# MAIN-FAN.net
KiCad netlist of a schematic drawn in Altium Designer
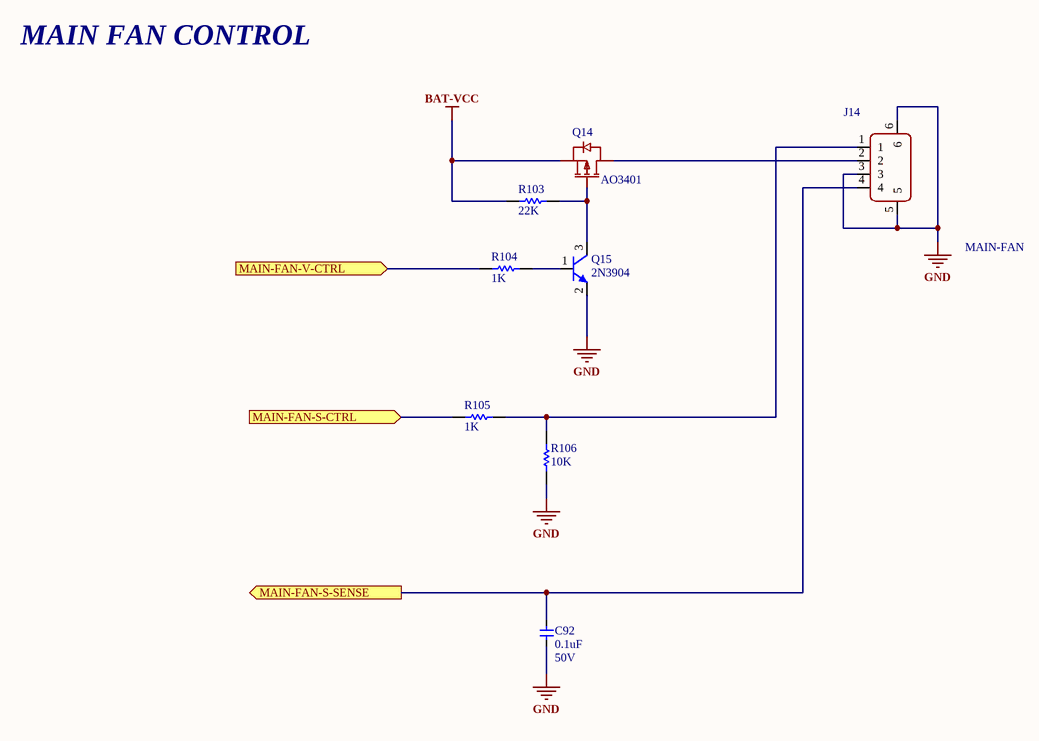
[diagram p0: MAIN-FAN .SchDoc]

(export (version "E")
  (design (tool "Eeschema 10.0.6"))
  (components
    (comp (ref "C92")
      (value "0.1uF")
      (footprint "CAP-0402")
      (fields (field (name "VOLTAGERATE") "50V"))
      (libsource (lib "DesignLibrary") (part "Capacitor-1"))
    )
    (comp (ref "J14")
      (value "MAIN-FAN")
      (footprint "CONN-SMD_4P-P2.00_XUNPU_WAFER-PH2.0-4PWB")
      (libsource (lib "DesignLibrary") (part "HDRx4"))
    )
    (comp (ref "Q14")
      (value "AO3401")
      (footprint "SOT23-3D")
      (libsource (lib "DesignLibrary") (part "P-MOS-SOT23"))
    )
    (comp (ref "Q15")
      (value "2N3904")
      (footprint "SOT23-3D")
      (libsource (lib "DesignLibrary") (part "NPN-SOT23"))
    )
    (comp (ref "R103")
      (value "22K")
      (footprint "RES-0402")
      (libsource (lib "DesignLibrary") (part "Resistor-1"))
    )
    (comp (ref "R104")
      (value "1K")
      (footprint "RES-0402")
      (libsource (lib "DesignLibrary") (part "Resistor-1"))
    )
    (comp (ref "R105")
      (value "1K")
      (footprint "RES-0402")
      (libsource (lib "DesignLibrary") (part "Resistor-1"))
    )
    (comp (ref "R106")
      (value "10K")
      (footprint "RES-0402")
      (libsource (lib "DesignLibrary") (part "Resistor-1"))
    )
  )
  (nets
    (net (code "1") (name "/MAIN-FAN-S-CTRL") (class "Default")
      (node (ref "R105") (pin "2") (pintype "passive"))
    )
    (net (code "2") (name "/MAIN-FAN-S-SENSE") (class "Default")
      (node (ref "C92") (pin "1") (pinfunction "1_1") (pintype "passive"))
      (node (ref "J14") (pin "4") (pinfunction "4_4") (pintype "passive"))
    )
    (net (code "3") (name "/MAIN-FAN-V-CTRL") (class "Default")
      (node (ref "R104") (pin "1") (pintype "passive"))
    )
    (net (code "4") (name "BAT-VCC") (class "Default")
      (node (ref "Q14") (pin "2") (pinfunction "S_2") (pintype "passive"))
      (node (ref "R103") (pin "1") (pintype "passive"))
    )
    (net (code "5") (name "GND") (class "Default")
      (node (ref "C92") (pin "2") (pinfunction "2_2") (pintype "passive"))
      (node (ref "J14") (pin "3") (pinfunction "3_3") (pintype "passive"))
      (node (ref "J14") (pin "5") (pinfunction "5_5") (pintype "passive"))
      (node (ref "J14") (pin "6") (pinfunction "6_6") (pintype "passive"))
      (node (ref "Q15") (pin "2") (pinfunction "E_2") (pintype "passive"))
      (node (ref "R106") (pin "1") (pintype "passive"))
    )
    (net (code "6") (name "Net-(J14-Pad1)") (class "Default")
      (node (ref "J14") (pin "1") (pinfunction "1_1") (pintype "passive"))
      (node (ref "R105") (pin "1") (pintype "passive"))
      (node (ref "R106") (pin "2") (pintype "passive"))
    )
    (net (code "7") (name "Net-(Q14-D)") (class "Default")
      (node (ref "J14") (pin "2") (pinfunction "2_2") (pintype "passive"))
      (node (ref "Q14") (pin "3") (pinfunction "D_3") (pintype "passive"))
    )
    (net (code "8") (name "Net-(Q14-G)") (class "Default")
      (node (ref "Q14") (pin "1") (pinfunction "G_1") (pintype "passive"))
      (node (ref "Q15") (pin "3") (pinfunction "C_3") (pintype "passive"))
      (node (ref "R103") (pin "2") (pintype "passive"))
    )
    (net (code "9") (name "Net-(Q15-B)") (class "Default")
      (node (ref "Q15") (pin "1") (pinfunction "B_1") (pintype "passive"))
      (node (ref "R104") (pin "2") (pintype "passive"))
    )
  )
)
